# dimmer.net
KiCad netlist of a schematic drawn in EAGLE
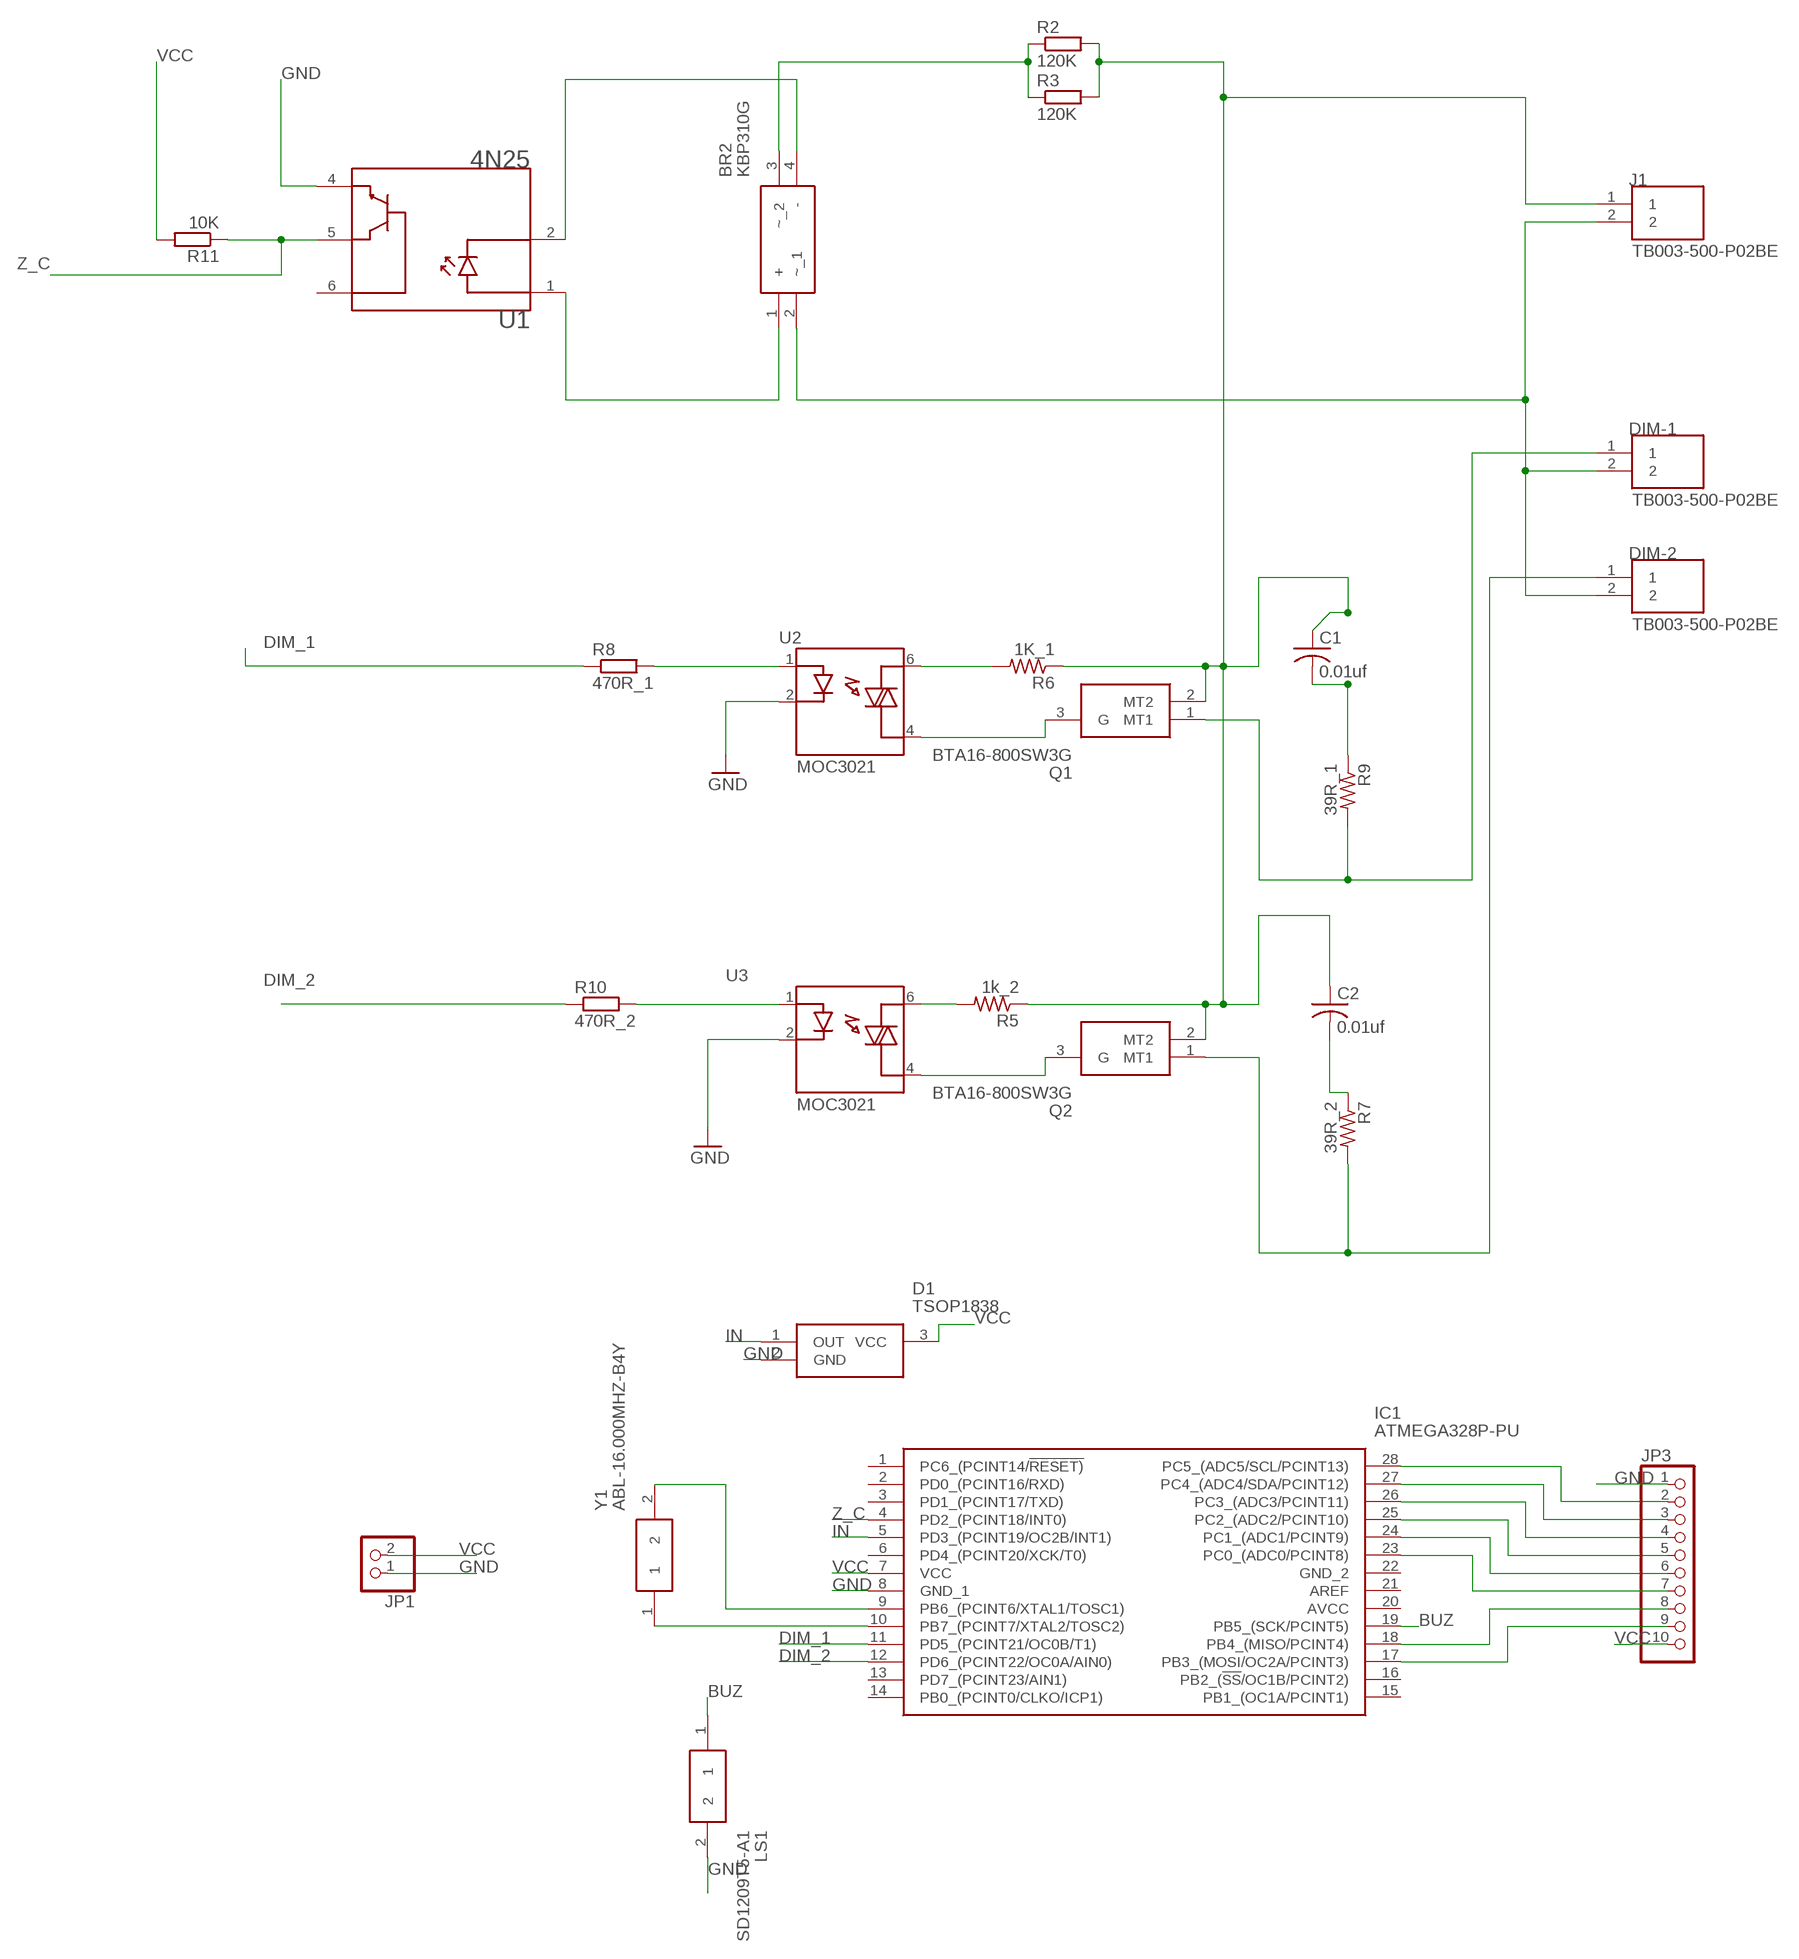
[diagram p0: schematic, sheet 1]

(export (version "E")
  (design (tool "Eeschema 10.0.6"))
  (components
    (comp (ref "BR2")
      (value "KBP310G")
      (footprint "eagle-import:TO385P508X1473X1168-4P")
      (fields (field (name "RS_PART_NUMBER") "9178856P"))
      (libsource (lib "eagle-import") (part "KBP310G"))
    )
    (comp (ref "C1")
      (value "0.01uf")
      (footprint "eagle-import:C150-072X183")
      (libsource (lib "eagle-import") (part "C-US150-072X183"))
    )
    (comp (ref "C2")
      (value "0.01uf")
      (footprint "eagle-import:C150-072X183")
      (libsource (lib "eagle-import") (part "C-US150-072X183"))
    )
    (comp (ref "D1")
      (value "TSOP1838")
      (footprint "eagle-import:TSOP4856")
      (fields (field (name "MOUSER_PART_NUMBER") "78-TSOP1838") (field (name "RS_PART_NUMBER") "2861425"))
      (libsource (lib "eagle-import") (part "TSOP1838"))
    )
    (comp (ref "DIM-1")
      (value "TB003-500-P02BE")
      (footprint "eagle-import:CUI_TB003-500-P02BE")
      (fields (field (name "MF") "CUI Inc."))
      (libsource (lib "eagle-import") (part "TB003-500-P02BE"))
    )
    (comp (ref "DIM-2")
      (value "TB003-500-P02BE")
      (footprint "eagle-import:CUI_TB003-500-P02BE")
      (fields (field (name "MF") "CUI Inc."))
      (libsource (lib "eagle-import") (part "TB003-500-P02BE"))
    )
    (comp (ref "IC1")
      (value "ATMEGA328P-PU")
      (footprint "eagle-import:DIP794W53P254L3467H457Q28N")
      (fields
        (field (name "MOUSER_PART_NUMBER") "556-ATMEGA328P-PU")
        (field (name "RS_PART_NUMBER") "9222142P")
      )
      (libsource (lib "eagle-import") (part "ATMEGA328P-PU"))
    )
    (comp (ref "J1")
      (value "TB003-500-P02BE")
      (footprint "eagle-import:CUI_TB003-500-P02BE")
      (fields (field (name "MF") "CUI Inc."))
      (libsource (lib "eagle-import") (part "TB003-500-P02BE"))
    )
    (comp (ref "JP1")
      (value "PINHD-1X2")
      (footprint "eagle-import:1X02")
      (libsource (lib "eagle-import") (part "PINHD-1X2"))
    )
    (comp (ref "JP3")
      (value "PINHD-1X10")
      (footprint "eagle-import:1X10")
      (libsource (lib "eagle-import") (part "PINHD-1X10"))
    )
    (comp (ref "LS1")
      (value "SD1209T5-A1")
      (footprint "eagle-import:SD1209T5-A1")
      (fields (field (name "MOUSER_PART_NUMBER") "810-SD1209T5-A1") (field (name "RS_PART_NUMBER") "1347311"))
      (libsource (lib "eagle-import") (part "SD1209T5-A1"))
    )
    (comp (ref "Q1")
      (value "BTA16-800SW3G")
      (footprint "eagle-import:TO254P482X997X2018-3P")
      (libsource (lib "eagle-import") (part "BTA16-800SW3G"))
    )
    (comp (ref "Q2")
      (value "BTA16-800SW3G")
      (footprint "eagle-import:TO254P482X997X2018-3P")
      (libsource (lib "eagle-import") (part "BTA16-800SW3G"))
    )
    (comp (ref "R2")
      (value "120K")
      (footprint "eagle-import:0617_22")
      (libsource (lib "eagle-import") (part "R-EU_0617/22"))
    )
    (comp (ref "R3")
      (value "120K")
      (footprint "eagle-import:0617_22")
      (libsource (lib "eagle-import") (part "R-EU_0617/22"))
    )
    (comp (ref "R5")
      (value "1k_2")
      (footprint "eagle-import:0309_12")
      (libsource (lib "eagle-import") (part "R-US_0309/12"))
    )
    (comp (ref "R6")
      (value "1K_1")
      (footprint "eagle-import:0309_12")
      (libsource (lib "eagle-import") (part "R-US_0309/12"))
    )
    (comp (ref "R7")
      (value "39R_2")
      (footprint "eagle-import:0309_12")
      (libsource (lib "eagle-import") (part "R-US_0309/12"))
    )
    (comp (ref "R8")
      (value "470R_1")
      (footprint "eagle-import:0207_10")
      (libsource (lib "eagle-import") (part "R-EU_0207/10"))
    )
    (comp (ref "R9")
      (value "39R_1")
      (footprint "eagle-import:0309_12")
      (libsource (lib "eagle-import") (part "R-US_0309/12"))
    )
    (comp (ref "R10")
      (value "470R_2")
      (footprint "eagle-import:0207_10")
      (libsource (lib "eagle-import") (part "R-EU_0207/10"))
    )
    (comp (ref "R11")
      (value "10K")
      (footprint "eagle-import:0207_10")
      (libsource (lib "eagle-import") (part "R-EU_0207/10"))
    )
    (comp (ref "U1")
      (value "4N25")
      (footprint "eagle-import:DIP762W50P254L712H400Q6N")
      (fields (field (name "MF") "Vishay Semiconductor"))
      (libsource (lib "eagle-import") (part "4N25"))
    )
    (comp (ref "U2")
      (value "MOC3021")
      (footprint "eagle-import:DIP762W45P254L889H508Q6")
      (fields (field (name "MF") "ON Semiconductor"))
      (libsource (lib "eagle-import") (part "MOC3021"))
    )
    (comp (ref "U3")
      (value "MOC3021")
      (footprint "eagle-import:DIP762W45P254L889H508Q6")
      (fields (field (name "MF") "ON Semiconductor"))
      (libsource (lib "eagle-import") (part "MOC3021"))
    )
    (comp (ref "Y1")
      (value "ABL-16.000MHZ-B4Y")
      (footprint "eagle-import:HC_49US_(AT49)PTH")
      (fields
        (field (name "MANUFACTURER_PART_NUMBER") "ABL-16.000MHz-B4Y")
        (field (name "MOUSER_PART_NUMBER") "815-ABL-16-B4Y")
      )
      (libsource (lib "eagle-import") (part "ABL-16.000MHZ-B4Y"))
    )
  )
  (nets
    (net (code "1") (name "/BUZ") (class "Default")
      (node (ref "IC1") (pin "19") (pinfunction "PB5_(SCK/PCINT5)_19") (pintype "bidirectional"))
      (node (ref "LS1") (pin "1") (pinfunction "1_1") (pintype "bidirectional"))
    )
    (net (code "2") (name "/DIM_1") (class "Default")
      (node (ref "IC1") (pin "11") (pinfunction "PD5_(PCINT21/OC0B/T1)_11") (pintype "bidirectional"))
      (node (ref "R8") (pin "1") (pinfunction "1_1") (pintype "passive"))
    )
    (net (code "3") (name "/DIM_2") (class "Default")
      (node (ref "IC1") (pin "12") (pinfunction "PD6_(PCINT22/OC0A/AIN0)_12") (pintype "bidirectional"))
      (node (ref "R10") (pin "1") (pinfunction "1_1") (pintype "passive"))
    )
    (net (code "4") (name "/IN") (class "Default")
      (node (ref "D1") (pin "1") (pinfunction "OUT_1") (pintype "bidirectional"))
      (node (ref "IC1") (pin "5") (pinfunction "PD3_(PCINT19/OC2B/INT1)_5") (pintype "bidirectional"))
    )
    (net (code "5") (name "/VCC") (class "Default")
      (node (ref "D1") (pin "3") (pinfunction "VCC_3") (pintype "bidirectional"))
      (node (ref "IC1") (pin "7") (pinfunction "VCC_7") (pintype "bidirectional"))
      (node (ref "JP1") (pin "2") (pinfunction "2_2") (pintype "passive"))
      (node (ref "JP3") (pin "10") (pinfunction "10_10") (pintype "passive"))
      (node (ref "R11") (pin "2") (pinfunction "2_2") (pintype "passive"))
    )
    (net (code "6") (name "/Z_C") (class "Default")
      (node (ref "IC1") (pin "4") (pinfunction "PD2_(PCINT18/INT0)_4") (pintype "bidirectional"))
      (node (ref "R11") (pin "1") (pinfunction "1_1") (pintype "passive"))
      (node (ref "U1") (pin "5") (pinfunction "C_5") (pintype "passive"))
    )
    (net (code "7") (name "GND") (class "Default")
      (node (ref "D1") (pin "2") (pinfunction "GND_2") (pintype "bidirectional"))
      (node (ref "IC1") (pin "8") (pinfunction "GND_1_8") (pintype "bidirectional"))
      (node (ref "JP1") (pin "1") (pinfunction "1_1") (pintype "passive"))
      (node (ref "JP3") (pin "1") (pinfunction "1_1") (pintype "passive"))
      (node (ref "LS1") (pin "2") (pinfunction "2_2") (pintype "bidirectional"))
      (node (ref "U1") (pin "4") (pinfunction "E_4") (pintype "passive"))
      (node (ref "U2") (pin "2") (pinfunction "CATODE_2") (pintype "passive"))
      (node (ref "U3") (pin "2") (pinfunction "CATODE_2") (pintype "passive"))
    )
    (net (code "8") (name "Net-(BR2-+)") (class "Default")
      (node (ref "BR2") (pin "1") (pinfunction "+_1") (pintype "bidirectional"))
      (node (ref "U1") (pin "1") (pinfunction "A_1") (pintype "passive"))
    )
    (net (code "9") (name "Net-(BR2--)") (class "Default")
      (node (ref "BR2") (pin "4") (pinfunction "-_4") (pintype "bidirectional"))
      (node (ref "U1") (pin "2") (pinfunction "K_2") (pintype "passive"))
    )
    (net (code "10") (name "Net-(BR2-~{_1})") (class "Default")
      (node (ref "BR2") (pin "2") (pinfunction "~{_1}_2") (pintype "bidirectional"))
      (node (ref "DIM-1") (pin "2") (pinfunction "2_2") (pintype "passive"))
      (node (ref "DIM-2") (pin "2") (pinfunction "2_2") (pintype "passive"))
      (node (ref "J1") (pin "2") (pinfunction "2_2") (pintype "passive"))
    )
    (net (code "11") (name "Net-(BR2-~{_2})") (class "Default")
      (node (ref "BR2") (pin "3") (pinfunction "~{_2}_3") (pintype "bidirectional"))
      (node (ref "R2") (pin "1") (pinfunction "1_1") (pintype "passive"))
      (node (ref "R3") (pin "1") (pinfunction "1_1") (pintype "passive"))
    )
    (net (code "12") (name "Net-(C1-Pad2)") (class "Default")
      (node (ref "C1") (pin "2") (pinfunction "2_2") (pintype "passive"))
      (node (ref "R9") (pin "1") (pinfunction "1_1") (pintype "passive"))
    )
    (net (code "13") (name "Net-(C2-Pad2)") (class "Default")
      (node (ref "C2") (pin "2") (pinfunction "2_2") (pintype "passive"))
      (node (ref "R7") (pin "1") (pinfunction "1_1") (pintype "passive"))
    )
    (net (code "14") (name "Net-(IC1-PB3_(MOSI{slash}OC2A{slash}PCINT3))") (class "Default")
      (node (ref "IC1") (pin "17") (pinfunction "PB3_(MOSI/OC2A/PCINT3)_17") (pintype "bidirectional"))
      (node (ref "JP3") (pin "9") (pinfunction "9_9") (pintype "passive"))
    )
    (net (code "15") (name "Net-(IC1-PB4_(MISO{slash}PCINT4))") (class "Default")
      (node (ref "IC1") (pin "18") (pinfunction "PB4_(MISO/PCINT4)_18") (pintype "bidirectional"))
      (node (ref "JP3") (pin "8") (pinfunction "8_8") (pintype "passive"))
    )
    (net (code "16") (name "Net-(IC1-PB6_(PCINT6{slash}XTAL1{slash}TOSC1))") (class "Default")
      (node (ref "IC1") (pin "9") (pinfunction "PB6_(PCINT6/XTAL1/TOSC1)_9") (pintype "bidirectional"))
      (node (ref "Y1") (pin "2") (pinfunction "2_2") (pintype "bidirectional"))
    )
    (net (code "17") (name "Net-(IC1-PB7_(PCINT7{slash}XTAL2{slash}TOSC2))") (class "Default")
      (node (ref "IC1") (pin "10") (pinfunction "PB7_(PCINT7/XTAL2/TOSC2)_10") (pintype "bidirectional"))
      (node (ref "Y1") (pin "1") (pinfunction "1_1") (pintype "bidirectional"))
    )
    (net (code "18") (name "Net-(IC1-PC0_(ADC0{slash}PCINT8))") (class "Default")
      (node (ref "IC1") (pin "23") (pinfunction "PC0_(ADC0/PCINT8)_23") (pintype "bidirectional"))
      (node (ref "JP3") (pin "7") (pinfunction "7_7") (pintype "passive"))
    )
    (net (code "19") (name "Net-(IC1-PC1_(ADC1{slash}PCINT9))") (class "Default")
      (node (ref "IC1") (pin "24") (pinfunction "PC1_(ADC1/PCINT9)_24") (pintype "bidirectional"))
      (node (ref "JP3") (pin "6") (pinfunction "6_6") (pintype "passive"))
    )
    (net (code "20") (name "Net-(IC1-PC2_(ADC2{slash}PCINT10))") (class "Default")
      (node (ref "IC1") (pin "25") (pinfunction "PC2_(ADC2/PCINT10)_25") (pintype "bidirectional"))
      (node (ref "JP3") (pin "5") (pinfunction "5_5") (pintype "passive"))
    )
    (net (code "21") (name "Net-(IC1-PC3_(ADC3{slash}PCINT11))") (class "Default")
      (node (ref "IC1") (pin "26") (pinfunction "PC3_(ADC3/PCINT11)_26") (pintype "bidirectional"))
      (node (ref "JP3") (pin "4") (pinfunction "4_4") (pintype "passive"))
    )
    (net (code "22") (name "Net-(IC1-PC4_(ADC4{slash}SDA{slash}PCINT12))") (class "Default")
      (node (ref "IC1") (pin "27") (pinfunction "PC4_(ADC4/SDA/PCINT12)_27") (pintype "bidirectional"))
      (node (ref "JP3") (pin "3") (pinfunction "3_3") (pintype "passive"))
    )
    (net (code "23") (name "Net-(IC1-PC5_(ADC5{slash}SCL{slash}PCINT13))") (class "Default")
      (node (ref "IC1") (pin "28") (pinfunction "PC5_(ADC5/SCL/PCINT13)_28") (pintype "bidirectional"))
      (node (ref "JP3") (pin "2") (pinfunction "2_2") (pintype "passive"))
    )
    (net (code "24") (name "Net-(Q1-G)") (class "Default")
      (node (ref "Q1") (pin "3") (pinfunction "G_3") (pintype "bidirectional"))
      (node (ref "U2") (pin "4") (pinfunction "MAIN_TERM2_4") (pintype "passive"))
    )
    (net (code "25") (name "Net-(Q1-MT1)") (class "Default")
      (node (ref "DIM-1") (pin "1") (pinfunction "1_1") (pintype "passive"))
      (node (ref "Q1") (pin "1") (pinfunction "MT1_1") (pintype "bidirectional"))
      (node (ref "R9") (pin "2") (pinfunction "2_2") (pintype "passive"))
    )
    (net (code "26") (name "Net-(Q1-MT2)") (class "Default")
      (node (ref "C1") (pin "1") (pinfunction "1_1") (pintype "passive"))
      (node (ref "C2") (pin "1") (pinfunction "1_1") (pintype "passive"))
      (node (ref "J1") (pin "1") (pinfunction "1_1") (pintype "passive"))
      (node (ref "Q1") (pin "2") (pinfunction "MT2_2") (pintype "bidirectional"))
      (node (ref "Q2") (pin "2") (pinfunction "MT2_2") (pintype "bidirectional"))
      (node (ref "R2") (pin "2") (pinfunction "2_2") (pintype "passive"))
      (node (ref "R3") (pin "2") (pinfunction "2_2") (pintype "passive"))
      (node (ref "R5") (pin "1") (pinfunction "1_1") (pintype "passive"))
      (node (ref "R6") (pin "1") (pinfunction "1_1") (pintype "passive"))
    )
    (net (code "27") (name "Net-(Q2-G)") (class "Default")
      (node (ref "Q2") (pin "3") (pinfunction "G_3") (pintype "bidirectional"))
      (node (ref "U3") (pin "4") (pinfunction "MAIN_TERM2_4") (pintype "passive"))
    )
    (net (code "28") (name "Net-(Q2-MT1)") (class "Default")
      (node (ref "DIM-2") (pin "1") (pinfunction "1_1") (pintype "passive"))
      (node (ref "Q2") (pin "1") (pinfunction "MT1_1") (pintype "bidirectional"))
      (node (ref "R7") (pin "2") (pinfunction "2_2") (pintype "passive"))
    )
    (net (code "29") (name "Net-(U2-ANODE)") (class "Default")
      (node (ref "R8") (pin "2") (pinfunction "2_2") (pintype "passive"))
      (node (ref "U2") (pin "1") (pinfunction "ANODE_1") (pintype "passive"))
    )
    (net (code "30") (name "Net-(U2-MAIN_TERM1)") (class "Default")
      (node (ref "R6") (pin "2") (pinfunction "2_2") (pintype "passive"))
      (node (ref "U2") (pin "6") (pinfunction "MAIN_TERM1_6") (pintype "passive"))
    )
    (net (code "31") (name "Net-(U3-ANODE)") (class "Default")
      (node (ref "R10") (pin "2") (pinfunction "2_2") (pintype "passive"))
      (node (ref "U3") (pin "1") (pinfunction "ANODE_1") (pintype "passive"))
    )
    (net (code "32") (name "Net-(U3-MAIN_TERM1)") (class "Default")
      (node (ref "R5") (pin "2") (pinfunction "2_2") (pintype "passive"))
      (node (ref "U3") (pin "6") (pinfunction "MAIN_TERM1_6") (pintype "passive"))
    )
    (net (code "33") (name "unconnected-(IC1-AREF-Pad21)") (class "Default")
      (node (ref "IC1") (pin "21") (pinfunction "AREF_21") (pintype "bidirectional"))
    )
    (net (code "34") (name "unconnected-(IC1-AVCC-Pad20)") (class "Default")
      (node (ref "IC1") (pin "20") (pinfunction "AVCC_20") (pintype "bidirectional"))
    )
    (net (code "35") (name "unconnected-(IC1-GND_2-Pad22)") (class "Default")
      (node (ref "IC1") (pin "22") (pinfunction "GND_2_22") (pintype "bidirectional"))
    )
    (net (code "36") (name "unconnected-(IC1-PB0_(PCINT0{slash}CLKO{slash}ICP1)-Pad14)") (class "Default")
      (node (ref "IC1") (pin "14") (pinfunction "PB0_(PCINT0/CLKO/ICP1)_14") (pintype "bidirectional"))
    )
    (net (code "37") (name "unconnected-(IC1-PB1_(OC1A{slash}PCINT1)-Pad15)") (class "Default")
      (node (ref "IC1") (pin "15") (pinfunction "PB1_(OC1A/PCINT1)_15") (pintype "bidirectional"))
    )
    (net (code "38") (name "unconnected-(IC1-PB2_(~{SS}{slash}OC1B{slash}PCINT2)-Pad16)") (class "Default")
      (node (ref "IC1") (pin "16") (pinfunction "PB2_(~{SS}/OC1B/PCINT2)_16") (pintype "bidirectional"))
    )
    (net (code "39") (name "unconnected-(IC1-PC6_(PCINT14{slash}~{RESET})-Pad1)") (class "Default")
      (node (ref "IC1") (pin "1") (pinfunction "PC6_(PCINT14/~{RESET})_1") (pintype "bidirectional"))
    )
    (net (code "40") (name "unconnected-(IC1-PD0_(PCINT16{slash}RXD)-Pad2)") (class "Default")
      (node (ref "IC1") (pin "2") (pinfunction "PD0_(PCINT16/RXD)_2") (pintype "bidirectional"))
    )
    (net (code "41") (name "unconnected-(IC1-PD1_(PCINT17{slash}TXD)-Pad3)") (class "Default")
      (node (ref "IC1") (pin "3") (pinfunction "PD1_(PCINT17/TXD)_3") (pintype "bidirectional"))
    )
    (net (code "42") (name "unconnected-(IC1-PD4_(PCINT20{slash}XCK{slash}T0)-Pad6)") (class "Default")
      (node (ref "IC1") (pin "6") (pinfunction "PD4_(PCINT20/XCK/T0)_6") (pintype "bidirectional"))
    )
    (net (code "43") (name "unconnected-(IC1-PD7_(PCINT23{slash}AIN1)-Pad13)") (class "Default")
      (node (ref "IC1") (pin "13") (pinfunction "PD7_(PCINT23/AIN1)_13") (pintype "bidirectional"))
    )
    (net (code "44") (name "unconnected-(U1-B-Pad6)") (class "Default")
      (node (ref "U1") (pin "6") (pinfunction "B_6") (pintype "passive"))
    )
  )
)
